# daughter-pots.net
KiCad netlist of a schematic drawn in EAGLE
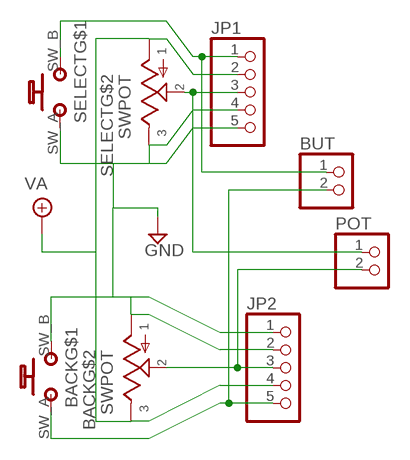
[diagram p0: schematic, sheet 1]

(export (version "E")
  (design (tool "Eeschema 10.0.6"))
  (components
    (comp (ref "BACK")
      (value "SWPOT")
      (footprint "eagle-import:SWPOT")
      (libsource (lib "eagle-import") (part "SWPOT"))
    )
    (comp (ref "BUT")
      (value "PINHD-1X2")
      (footprint "eagle-import:1X02")
      (libsource (lib "eagle-import") (part "PINHD-1X2"))
    )
    (comp (ref "JP1")
      (value "PINHD-1X5")
      (footprint "eagle-import:1X05")
      (libsource (lib "eagle-import") (part "PINHD-1X5"))
    )
    (comp (ref "JP2")
      (value "PINHD-1X5")
      (footprint "eagle-import:1X05")
      (libsource (lib "eagle-import") (part "PINHD-1X5"))
    )
    (comp (ref "POT")
      (value "PINHD-1X2")
      (footprint "eagle-import:1X02")
      (libsource (lib "eagle-import") (part "PINHD-1X2"))
    )
    (comp (ref "SELECT")
      (value "SWPOT")
      (footprint "eagle-import:SWPOT")
      (libsource (lib "eagle-import") (part "SWPOT"))
    )
  )
  (nets
    (net (code "1") (name "GND") (class "Default")
      (node (ref "BACK") (pin "POT_B") (pinfunction "POT_B_POT_B") (pintype "passive"))
      (node (ref "BACK") (pin "SW_B") (pinfunction "B_B_SW_B") (pintype "passive"))
      (node (ref "JP1") (pin "4") (pinfunction "4_4") (pintype "passive"))
      (node (ref "JP1") (pin "5") (pinfunction "5_5") (pintype "passive"))
      (node (ref "JP2") (pin "1") (pinfunction "1_1") (pintype "passive"))
      (node (ref "JP2") (pin "2") (pinfunction "2_2") (pintype "passive"))
      (node (ref "SELECT") (pin "POT_A") (pinfunction "POT_A_POT_A") (pintype "passive"))
      (node (ref "SELECT") (pin "SW_A") (pinfunction "B_A_SW_A") (pintype "passive"))
    )
    (net (code "2") (name "Net-(BACK-PadPOT_W)") (class "Default")
      (node (ref "BACK") (pin "POT_W") (pinfunction "POT_W_POT_W") (pintype "passive"))
      (node (ref "JP2") (pin "3") (pinfunction "3_3") (pintype "passive"))
      (node (ref "POT") (pin "2") (pinfunction "2_2") (pintype "passive"))
    )
    (net (code "3") (name "Net-(BACKA-B_A)") (class "Default")
      (node (ref "BACK") (pin "SW_A") (pinfunction "B_A_SW_A") (pintype "passive"))
      (node (ref "BUT") (pin "2") (pinfunction "2_2") (pintype "passive"))
      (node (ref "JP2") (pin "5") (pinfunction "5_5") (pintype "passive"))
    )
    (net (code "4") (name "Net-(JP1-Pad3)") (class "Default")
      (node (ref "JP1") (pin "3") (pinfunction "3_3") (pintype "passive"))
      (node (ref "POT") (pin "1") (pinfunction "1_1") (pintype "passive"))
      (node (ref "SELECT") (pin "POT_W") (pinfunction "POT_W_POT_W") (pintype "passive"))
    )
    (net (code "5") (name "Net-(SELECTA-B_B)") (class "Default")
      (node (ref "BUT") (pin "1") (pinfunction "1_1") (pintype "passive"))
      (node (ref "JP1") (pin "1") (pinfunction "1_1") (pintype "passive"))
      (node (ref "SELECT") (pin "SW_B") (pinfunction "B_B_SW_B") (pintype "passive"))
    )
    (net (code "6") (name "VA") (class "Default")
      (node (ref "BACK") (pin "POT_A") (pinfunction "POT_A_POT_A") (pintype "passive"))
      (node (ref "JP1") (pin "2") (pinfunction "2_2") (pintype "passive"))
      (node (ref "JP2") (pin "4") (pinfunction "4_4") (pintype "passive"))
      (node (ref "SELECT") (pin "POT_B") (pinfunction "POT_B_POT_B") (pintype "passive"))
    )
  )
)
